# HX711.net
KiCad netlist of a schematic drawn in Altium Designer
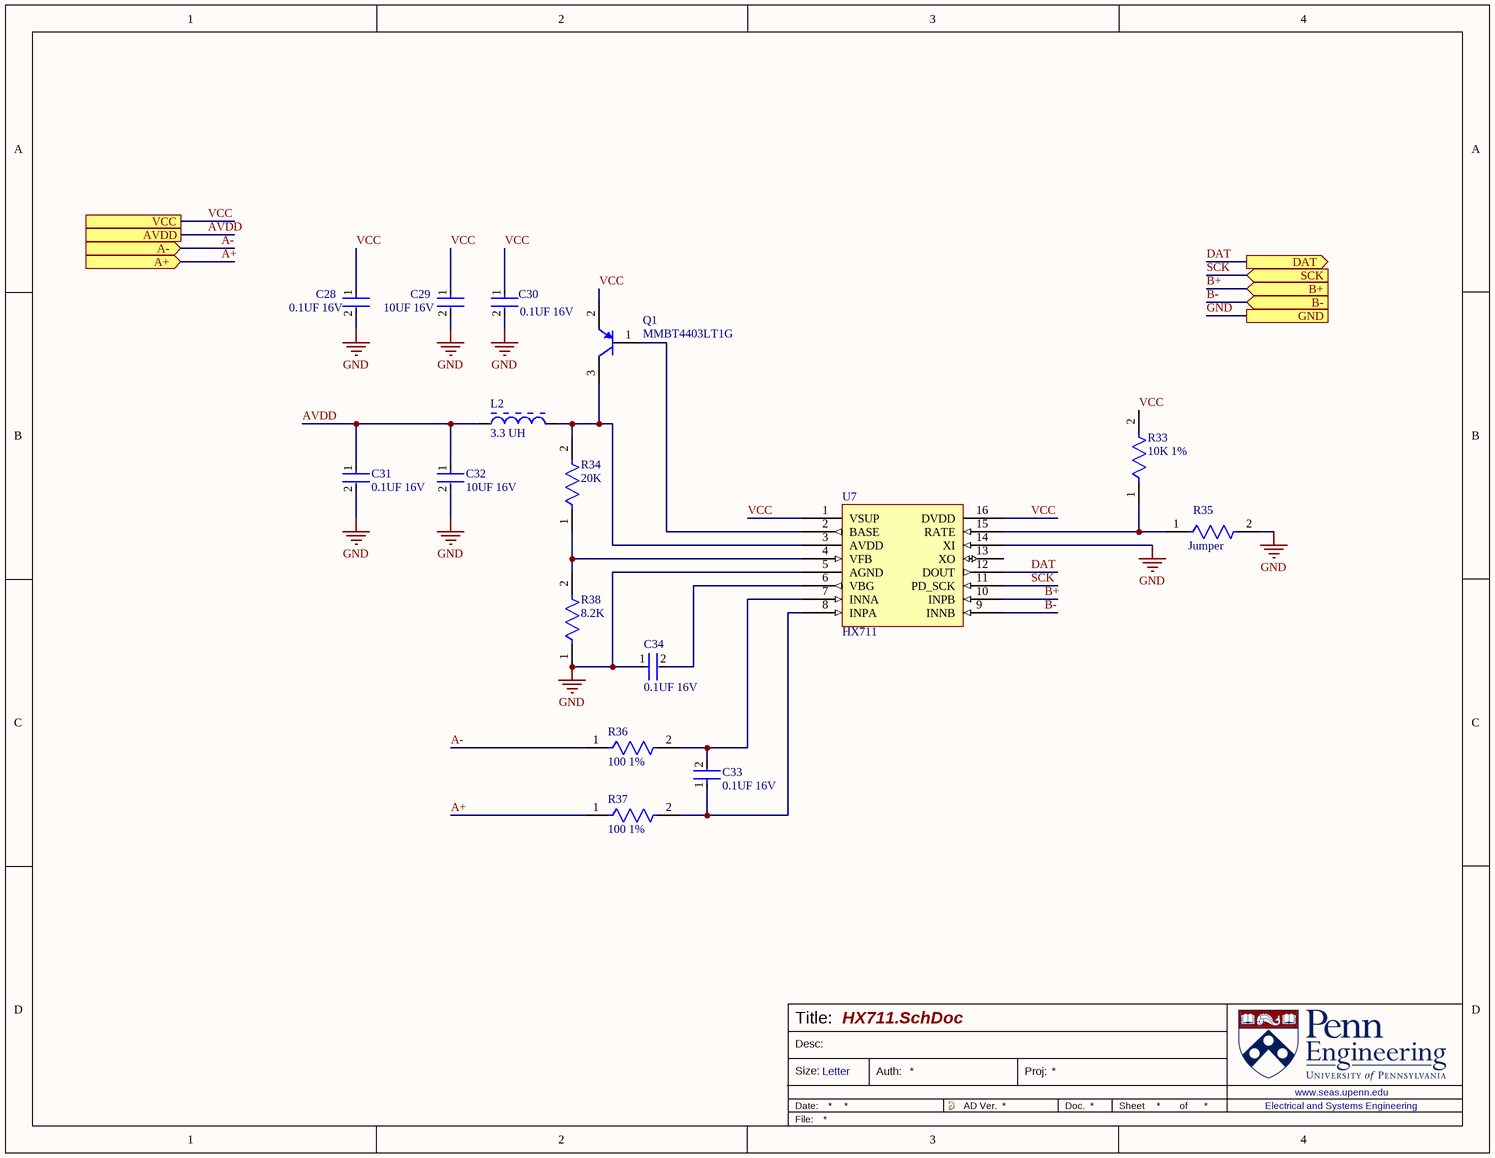
[diagram p0: HX711.SchDoc]

(export (version "E")
  (design (tool "Eeschema 10.0.6"))
  (components
    (comp (ref "C28")
      (value "0.1UF 16V")
      (footprint "FP-CC0402-MFG")
      (description "CC0402 100 nF X7R 10.00% 25 V")
      (fields
        (field (name "MANUFACTURER PART NUMBER") "CC0402KPX7R8BB104")
        (field (name "MANUFACTURER") "YAGEO")
      )
      (libsource (lib "Altium Content Vault") (part "11868f565c42a9108669ba33697ecf6"))
    )
    (comp (ref "C29")
      (value "10UF 16V")
      (footprint "FP-CC0603-DB-MFG")
      (description "CAP CER 10UF 6.3V X5R 0603")
      (fields (field (name "TOLERANCE") "20%"))
      (libsource (lib "Altium Content Vault") (part "e9c51b7dd13d4faca003ae77663ab08"))
    )
    (comp (ref "C30")
      (value "0.1UF 16V")
      (footprint "FP-CC0402-MFG")
      (description "CC0402 100 nF X7R 10.00% 25 V")
      (fields
        (field (name "MANUFACTURER PART NUMBER") "CC0402KPX7R8BB104")
        (field (name "MANUFACTURER") "YAGEO")
      )
      (libsource (lib "Altium Content Vault") (part "11868f565c42a9108669ba33697ecf6"))
    )
    (comp (ref "C31")
      (value "0.1UF 16V")
      (footprint "FP-CC0402-MFG")
      (description "CC0402 100 nF X7R 10.00% 25 V")
      (fields
        (field (name "MANUFACTURER PART NUMBER") "CC0402KPX7R8BB104")
        (field (name "MANUFACTURER") "YAGEO")
      )
      (libsource (lib "Altium Content Vault") (part "11868f565c42a9108669ba33697ecf6"))
    )
    (comp (ref "C32")
      (value "10UF 16V")
      (footprint "FP-CC0603-DB-MFG")
      (description "CAP CER 10UF 6.3V X5R 0603")
      (fields (field (name "TOLERANCE") "20%"))
      (libsource (lib "Altium Content Vault") (part "e9c51b7dd13d4faca003ae77663ab08"))
    )
    (comp (ref "C33")
      (value "0.1UF 16V")
      (footprint "FP-CC0402-MFG")
      (description "CC0402 100 nF X7R 10.00% 25 V")
      (fields
        (field (name "MANUFACTURER PART NUMBER") "CC0402KPX7R8BB104")
        (field (name "MANUFACTURER") "YAGEO")
      )
      (libsource (lib "Altium Content Vault") (part "11868f565c42a9108669ba33697ecf6"))
    )
    (comp (ref "C34")
      (value "0.1UF 16V")
      (footprint "FP-CC0402-MFG")
      (description "CC0402 100 nF X7R 10.00% 25 V")
      (fields
        (field (name "MANUFACTURER PART NUMBER") "CC0402KPX7R8BB104")
        (field (name "MANUFACTURER") "YAGEO")
      )
      (libsource (lib "Altium Content Vault") (part "11868f565c42a9108669ba33697ecf6"))
    )
    (comp (ref "L2")
      (value "3.3 UH")
      (footprint "BOUR-SRN3015-2_V")
      (fields (field (name "MANUFACTURER") "Bourns") (field (name "PARTNUMBER") "SRN3015-3R3M"))
      (libsource (lib "Altium Content Vault") (part "BOUR-IND-2A"))
    )
    (comp (ref "Q1")
      (value "MMBT4403LT1G")
      (footprint "ONSC-SOT-23-3-318-08_V")
      (description "Switching Transistor, PNP Silicon, 3-Pin SOT-23, Pb-Free, Tape and Reel")
      (fields (field (name "MANUFACTURER") "On Semiconductor"))
      (libsource (lib "Altium Content Vault") (part "ONSC-PNP-B1E2C3-3"))
    )
    (comp (ref "R33")
      (value "10K 1%")
      (footprint "FP-RNCP0603-IPC_A")
      (description "10kΩ ±1% 0.125W 0603 High Power Anti-Sulfur Thin Film Chip Resistor")
      (fields (field (name "TOLERANCE") "1%"))
      (libsource (lib "Altium Content Vault") (part "1029c3af85768c4190bb7ad29bc67b5"))
    )
    (comp (ref "R34")
      (value "20K")
      (footprint "FP-RMCF0402-IPC_A")
      (description "20kΩ ±1% 0.063W 0402 Thick Film Chip Resistor AEC-Q200 compliant")
      (fields (field (name "TOLERANCE") "1%"))
      (libsource (lib "Altium Content Vault") (part "1029c3af85768c4190bb7ad29bc67b5"))
    )
    (comp (ref "R35")
      (value "Jumper")
      (footprint "FP-RMCF0603-MFG")
      (description "RES 0 OHM JUMPER 1/10W 0603")
      (fields
        (field (name "MANUFACTURER PART NUMBER") "RMCF0603ZT0R00")
        (field (name "OCTOPART") "https://octopart.com/rmcf0603zt0r00-stackpole+electronics-19213618")
      )
      (libsource (lib "Altium Content Vault") (part "1029c3af85768c4190bb7ad29bc67b5"))
    )
    (comp (ref "R36")
      (value "100 1%")
      (footprint "FP-RMCF0603-IPC_C")
      (description "100Ω ±1% 0.1W 0603 Thick Film Chip Resistor AEC-Q200 compliant")
      (fields (field (name "TOLERANCE") "1%"))
      (libsource (lib "Altium Content Vault") (part "1029c3af85768c4190bb7ad29bc67b5"))
    )
    (comp (ref "R37")
      (value "100 1%")
      (footprint "FP-RMCF0603-IPC_C")
      (description "100Ω ±1% 0.1W 0603 Thick Film Chip Resistor AEC-Q200 compliant")
      (fields (field (name "TOLERANCE") "1%"))
      (libsource (lib "Altium Content Vault") (part "1029c3af85768c4190bb7ad29bc67b5"))
    )
    (comp (ref "R38")
      (value "8.2K")
      (footprint "FP-RMCF0603-IPC_A")
      (description "8.2kΩ ±5% 0.1W 0603 Thick Film Chip Resistor AEC-Q200 compliant")
      (fields (field (name "TOLERANCE") "5%"))
      (libsource (lib "Altium Content Vault") (part "1029c3af85768c4190bb7ad29bc67b5"))
    )
    (comp (ref "U7")
      (value "HX711")
      (footprint "SOIC127P600X160-16N")
      (description "ADC, Delta-Sigma, 24-Bit, 1 Func, 2 Channel, Serial Access, PDSO16")
      (libsource (lib "University of Pennsylvania (ESE Labs)") (part "HX711-Symbol-1"))
    )
  )
  (nets
    (net (code "1") (name "/A+") (class "Default")
      (node (ref "R37") (pin "1") (pinfunction "1_1") (pintype "passive"))
    )
    (net (code "2") (name "/A-") (class "Default")
      (node (ref "R36") (pin "1") (pinfunction "1_1") (pintype "passive"))
    )
    (net (code "3") (name "/AVDD") (class "Default")
      (node (ref "C31") (pin "1") (pinfunction "1_1") (pintype "passive"))
      (node (ref "C32") (pin "1") (pinfunction "1_1") (pintype "passive"))
      (node (ref "L2") (pin "1") (pinfunction "1_1") (pintype "passive"))
    )
    (net (code "4") (name "/B+") (class "Default")
      (node (ref "U7") (pin "10") (pinfunction "INPB_10") (pintype "input"))
    )
    (net (code "5") (name "/B-") (class "Default")
      (node (ref "U7") (pin "9") (pinfunction "INNB_9") (pintype "input"))
    )
    (net (code "6") (name "/DAT") (class "Default")
      (node (ref "U7") (pin "12") (pinfunction "DOUT_12") (pintype "output"))
    )
    (net (code "7") (name "/SCK") (class "Default")
      (node (ref "U7") (pin "11") (pinfunction "PD_SCK_11") (pintype "input"))
    )
    (net (code "8") (name "/VCC") (class "Default")
      (node (ref "C28") (pin "1") (pinfunction "1_1") (pintype "passive"))
      (node (ref "C29") (pin "1") (pinfunction "1_1") (pintype "passive"))
      (node (ref "C30") (pin "1") (pinfunction "1_1") (pintype "passive"))
      (node (ref "Q1") (pin "2") (pinfunction "E_2") (pintype "passive"))
      (node (ref "R33") (pin "2") (pinfunction "2_2") (pintype "passive"))
      (node (ref "U7") (pin "1") (pinfunction "VSUP_1") (pintype "power_in"))
      (node (ref "U7") (pin "16") (pinfunction "DVDD_16") (pintype "power_in"))
    )
    (net (code "9") (name "GND") (class "Default")
      (node (ref "C28") (pin "2") (pinfunction "2_2") (pintype "passive"))
      (node (ref "C29") (pin "2") (pinfunction "2_2") (pintype "passive"))
      (node (ref "C30") (pin "2") (pinfunction "2_2") (pintype "passive"))
      (node (ref "C31") (pin "2") (pinfunction "2_2") (pintype "passive"))
      (node (ref "C32") (pin "2") (pinfunction "2_2") (pintype "passive"))
      (node (ref "C34") (pin "1") (pinfunction "1_1") (pintype "passive"))
      (node (ref "R35") (pin "2") (pinfunction "2_2") (pintype "passive"))
      (node (ref "R38") (pin "1") (pinfunction "1_1") (pintype "passive"))
      (node (ref "U7") (pin "14") (pinfunction "XI_14") (pintype "input"))
      (node (ref "U7") (pin "5") (pinfunction "AGND_5") (pintype "power_in"))
    )
    (net (code "10") (name "Net-(Q1-B)") (class "Default")
      (node (ref "Q1") (pin "1") (pinfunction "B_1") (pintype "passive"))
      (node (ref "U7") (pin "2") (pinfunction "BASE_2") (pintype "output"))
    )
    (net (code "11") (name "Net-(Q1-C)") (class "Default")
      (node (ref "L2") (pin "2") (pinfunction "2_2") (pintype "passive"))
      (node (ref "Q1") (pin "3") (pinfunction "C_3") (pintype "passive"))
      (node (ref "R34") (pin "2") (pinfunction "2_2") (pintype "passive"))
      (node (ref "U7") (pin "3") (pinfunction "AVDD_3") (pintype "power_in"))
    )
    (net (code "12") (name "Net-(U7-INNA)") (class "Default")
      (node (ref "C33") (pin "2") (pinfunction "2_2") (pintype "passive"))
      (node (ref "R36") (pin "2") (pinfunction "2_2") (pintype "passive"))
      (node (ref "U7") (pin "7") (pinfunction "INNA_7") (pintype "input"))
    )
    (net (code "13") (name "Net-(U7-INPA)") (class "Default")
      (node (ref "C33") (pin "1") (pinfunction "1_1") (pintype "passive"))
      (node (ref "R37") (pin "2") (pinfunction "2_2") (pintype "passive"))
      (node (ref "U7") (pin "8") (pinfunction "INPA_8") (pintype "input"))
    )
    (net (code "14") (name "Net-(U7-RATE)") (class "Default")
      (node (ref "R33") (pin "1") (pinfunction "1_1") (pintype "passive"))
      (node (ref "R35") (pin "1") (pinfunction "1_1") (pintype "passive"))
      (node (ref "U7") (pin "15") (pinfunction "RATE_15") (pintype "input"))
    )
    (net (code "15") (name "Net-(U7-VBG)") (class "Default")
      (node (ref "C34") (pin "2") (pinfunction "2_2") (pintype "passive"))
      (node (ref "U7") (pin "6") (pinfunction "VBG_6") (pintype "output"))
    )
    (net (code "16") (name "Net-(U7-VFB)") (class "Default")
      (node (ref "R34") (pin "1") (pinfunction "1_1") (pintype "passive"))
      (node (ref "R38") (pin "2") (pinfunction "2_2") (pintype "passive"))
      (node (ref "U7") (pin "4") (pinfunction "VFB_4") (pintype "input"))
    )
    (net (code "17") (name "unconnected-(U7-XO-Pad13)") (class "Default")
      (node (ref "U7") (pin "13") (pinfunction "XO_13") (pintype "bidirectional"))
    )
  )
)
